# 3_Controller_A20_Ethernet.net
KiCad netlist of a schematic drawn in Altium Designer
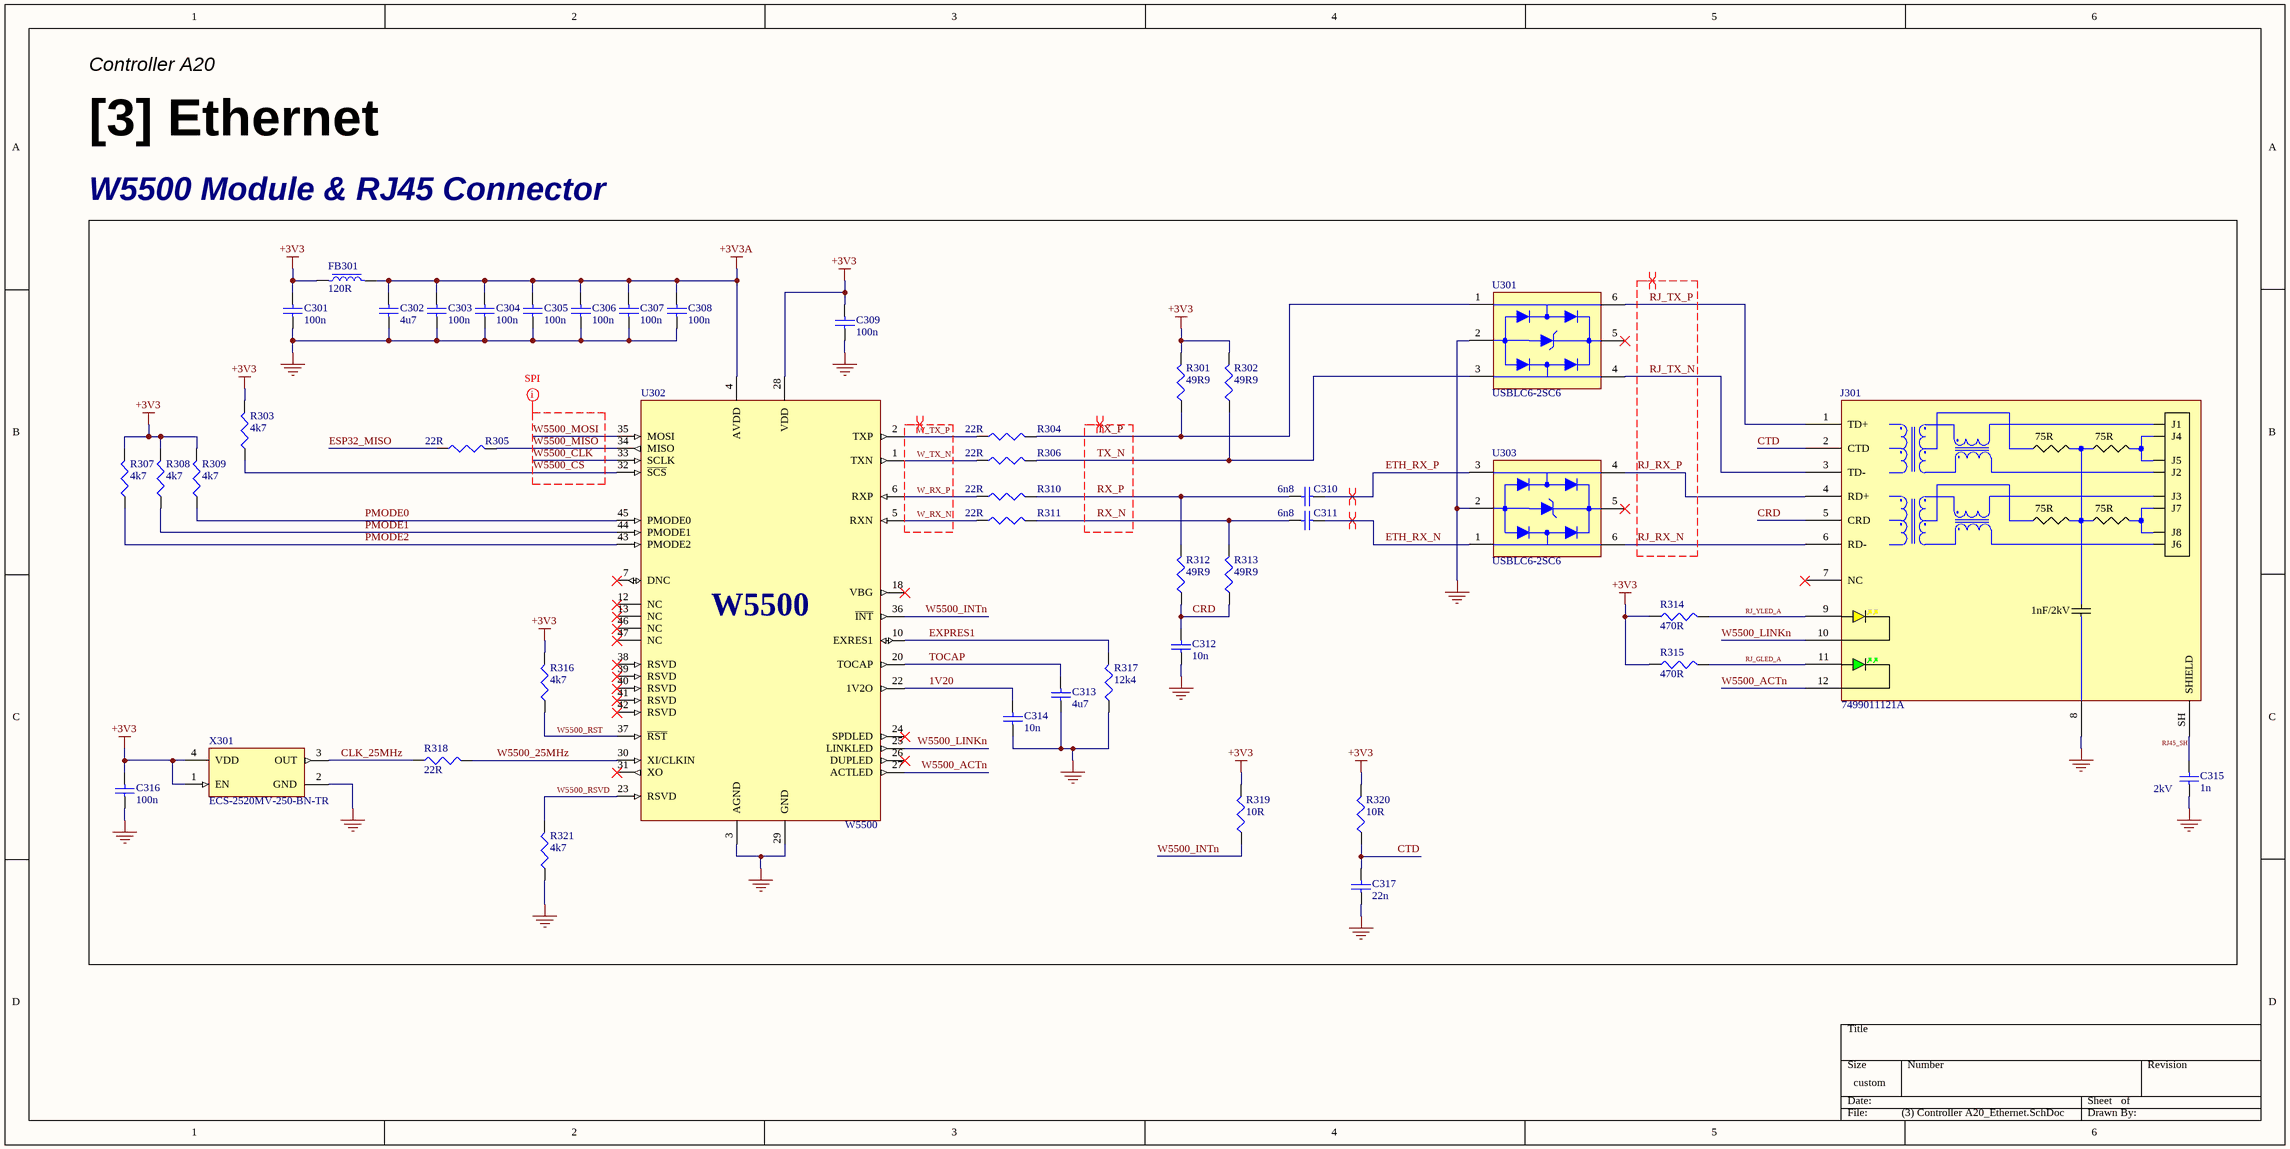
[diagram p0: (3) Controller A20_Ethernet.SchDoc]

(export (version "E")
  (design (tool "Eeschema 10.0.6"))
  (components
    (comp (ref "C301")
      (value "100n")
      (footprint "C0603")
      (description "0.1 µF ±10% 50V Ceramic Capacitor X7R 0603 (1608 Metric)")
      (fields (field (name "MANUFACTURER") "KEMET") (field (name "MFR. PART #") "C0603C104K5RACTU"))
      (libsource (lib "Symbols") (part "CAP 100nF 50V"))
    )
    (comp (ref "C302")
      (value "4u7")
      (footprint "C0805")
      (description "4.7 µF ±20% 50V Ceramic Capacitor X7R 0805 (2012 Metric)")
      (fields
        (field (name "MANUFACTURER") "Murata Electronics")
        (field (name "MFR. PART #") "GRM21BZ71H475ME15K")
      )
      (libsource (lib "Symbols") (part "CAP 4.7uF 50V"))
    )
    (comp (ref "C303")
      (value "100n")
      (footprint "C0603")
      (description "0.1 µF ±10% 50V Ceramic Capacitor X7R 0603 (1608 Metric)")
      (fields (field (name "MANUFACTURER") "KEMET") (field (name "MFR. PART #") "C0603C104K5RACTU"))
      (libsource (lib "Symbols") (part "CAP 100nF 50V"))
    )
    (comp (ref "C304")
      (value "100n")
      (footprint "C0603")
      (description "0.1 µF ±10% 50V Ceramic Capacitor X7R 0603 (1608 Metric)")
      (fields (field (name "MANUFACTURER") "KEMET") (field (name "MFR. PART #") "C0603C104K5RACTU"))
      (libsource (lib "Symbols") (part "CAP 100nF 50V"))
    )
    (comp (ref "C305")
      (value "100n")
      (footprint "C0603")
      (description "0.1 µF ±10% 50V Ceramic Capacitor X7R 0603 (1608 Metric)")
      (fields (field (name "MANUFACTURER") "KEMET") (field (name "MFR. PART #") "C0603C104K5RACTU"))
      (libsource (lib "Symbols") (part "CAP 100nF 50V"))
    )
    (comp (ref "C306")
      (value "100n")
      (footprint "C0603")
      (description "0.1 µF ±10% 50V Ceramic Capacitor X7R 0603 (1608 Metric)")
      (fields (field (name "MANUFACTURER") "KEMET") (field (name "MFR. PART #") "C0603C104K5RACTU"))
      (libsource (lib "Symbols") (part "CAP 100nF 50V"))
    )
    (comp (ref "C307")
      (value "100n")
      (footprint "C0603")
      (description "0.1 µF ±10% 50V Ceramic Capacitor X7R 0603 (1608 Metric)")
      (fields (field (name "MANUFACTURER") "KEMET") (field (name "MFR. PART #") "C0603C104K5RACTU"))
      (libsource (lib "Symbols") (part "CAP 100nF 50V"))
    )
    (comp (ref "C308")
      (value "100n")
      (footprint "C0603")
      (description "0.1 µF ±10% 50V Ceramic Capacitor X7R 0603 (1608 Metric)")
      (fields (field (name "MANUFACTURER") "KEMET") (field (name "MFR. PART #") "C0603C104K5RACTU"))
      (libsource (lib "Symbols") (part "CAP 100nF 50V"))
    )
    (comp (ref "C309")
      (value "100n")
      (footprint "C0603")
      (description "0.1 µF ±10% 50V Ceramic Capacitor X7R 0603 (1608 Metric)")
      (fields (field (name "MANUFACTURER") "KEMET") (field (name "MFR. PART #") "C0603C104K5RACTU"))
      (libsource (lib "Symbols") (part "CAP 100nF 50V"))
    )
    (comp (ref "C310")
      (value "6n8")
      (footprint "C0402")
      (description "6800 pF ±10% 100V Ceramic Capacitor X7R 0402 (1005 Metric)")
      (fields
        (field (name "MANUFACTURER") "Samsung Electro-Mechanics")
        (field (name "MFR. PART #") "CL05B682KC5VPNC")
      )
      (libsource (lib "Symbols") (part "CAP 6.8nF 100V"))
    )
    (comp (ref "C311")
      (value "6n8")
      (footprint "C0402")
      (description "6800 pF ±10% 100V Ceramic Capacitor X7R 0402 (1005 Metric)")
      (fields
        (field (name "MANUFACTURER") "Samsung Electro-Mechanics")
        (field (name "MFR. PART #") "CL05B682KC5VPNC")
      )
      (libsource (lib "Symbols") (part "CAP 6.8nF 100V"))
    )
    (comp (ref "C312")
      (value "10n")
      (footprint "C0402")
      (description "10000 pF ±10% 50V Ceramic Capacitor X7R 0402 (1005 Metric)")
      (fields (field (name "MANUFACTURER") "KEMET") (field (name "MFR. PART #") "C0402C103K5REC7411"))
      (libsource (lib "Symbols") (part "CAP 10nF 50V"))
    )
    (comp (ref "C313")
      (value "4u7")
      (footprint "C0805")
      (description "4.7 µF ±20% 50V Ceramic Capacitor X7R 0805 (2012 Metric)")
      (fields
        (field (name "MANUFACTURER") "Murata Electronics")
        (field (name "MFR. PART #") "GRM21BZ71H475ME15K")
      )
      (libsource (lib "Symbols") (part "CAP 4.7uF 50V"))
    )
    (comp (ref "C314")
      (value "10n")
      (footprint "C0402")
      (description "10000 pF ±10% 50V Ceramic Capacitor X7R 0402 (1005 Metric)")
      (fields (field (name "MANUFACTURER") "KEMET") (field (name "MFR. PART #") "C0402C103K5REC7411"))
      (libsource (lib "Symbols") (part "CAP 10nF 50V"))
    )
    (comp (ref "C315")
      (value "1n")
      (footprint "C1206")
      (description "2kV 1nF X7R ±10% 1206 Multilayer Ceramic Capacitors MLCC - SMD/SMT ROHS")
      (fields
        (field (name "MANUFACTURER") "Johanson Dielectrics")
        (field (name "MFR. PART #") "202R18W102KV4E")
      )
      (libsource (lib "Symbols") (part "CAP 1nF 2kV"))
    )
    (comp (ref "C316")
      (value "100n")
      (footprint "C0603")
      (description "0.1 µF ±10% 50V Ceramic Capacitor X7R 0603 (1608 Metric)")
      (fields (field (name "MANUFACTURER") "KEMET") (field (name "MFR. PART #") "C0603C104K5RACTU"))
      (libsource (lib "Symbols") (part "CAP 100nF 50V"))
    )
    (comp (ref "C317")
      (value "22n")
      (footprint "C0402")
      (description "0.022 µF ±10% 50V Ceramic Capacitor X7R 0402 (1005 Metric)")
      (fields (field (name "MANUFACTURER") "YAGEO") (field (name "MFR. PART #") "CC0402KRX7R9BB223"))
      (libsource (lib "Symbols") (part "CAP 22nF 50V"))
    )
    (comp (ref "FB301")
      (value "120R")
      (footprint "FB0402")
      (description "120 Ohms @ 100 MHz 1 Power Line Ferrite Bead 0402 (1005 Metric) 2A 55mOhm")
      (fields
        (field (name "MANUFACTURER") "Murata Electronics")
        (field (name "MFR. PART #") "BLM15PX121SN1D")
      )
      (libsource (lib "Symbols") (part "BLM15PX121SN1D Ferrite Bead 120Ω"))
    )
    (comp (ref "J301")
      (value "7499011121A")
      (footprint "RJ45 TH Connector")
      (description "1 Port RJ45 with Magnetics Through Hole 10/100 Base-T, AutoMDIX")
      (fields (field (name "MANUFACTURER") "Würth Elektronik"))
      (libsource (lib "Symbols") (part "7499011121A RJ45 Connector"))
    )
    (comp (ref "R301")
      (value "49R9")
      (footprint "R0402")
      (description "49.9 Ohms ±1% 0.063W, 1/16W Chip Resistor 0402 (1005 Metric) Moisture Resistant Thick Film")
      (fields (field (name "MANUFACTURER") "YAGEO") (field (name "MFR. PART #") "RC0402FR-0749R9L"))
      (libsource (lib "Symbols") (part "RES 49.9R"))
    )
    (comp (ref "R302")
      (value "49R9")
      (footprint "R0402")
      (description "49.9 Ohms ±1% 0.063W, 1/16W Chip Resistor 0402 (1005 Metric) Moisture Resistant Thick Film")
      (fields (field (name "MANUFACTURER") "YAGEO") (field (name "MFR. PART #") "RC0402FR-0749R9L"))
      (libsource (lib "Symbols") (part "RES 49.9R"))
    )
    (comp (ref "R303")
      (value "4k7")
      (footprint "R0603")
      (description "4.7 kOhms ±1% 0.1W, 1/10W Chip Resistor 0603 (1608 Metric) Moisture Resistant Thick Film")
      (fields (field (name "MANUFACTURER") "YAGEO") (field (name "MFR. PART #") "RC0603FR-074K7L"))
      (libsource (lib "Symbols") (part "RES 4.7k"))
    )
    (comp (ref "R304")
      (value "22R")
      (footprint "R0402")
      (description "22 Ohms ±1% 0.063W, 1/16W Chip Resistor 0402 (1005 Metric) Moisture Resistant Thick Film")
      (fields (field (name "MANUFACTURER") "YAGEO") (field (name "MFR. PART #") "RC0402FR-0722RL"))
      (libsource (lib "Symbols") (part "RES 22R"))
    )
    (comp (ref "R305")
      (value "22R")
      (footprint "R0402")
      (description "22 Ohms ±1% 0.063W, 1/16W Chip Resistor 0402 (1005 Metric) Moisture Resistant Thick Film")
      (fields (field (name "MANUFACTURER") "YAGEO") (field (name "MFR. PART #") "RC0402FR-0722RL"))
      (libsource (lib "Symbols") (part "RES 22R"))
    )
    (comp (ref "R306")
      (value "22R")
      (footprint "R0402")
      (description "22 Ohms ±1% 0.063W, 1/16W Chip Resistor 0402 (1005 Metric) Moisture Resistant Thick Film")
      (fields (field (name "MANUFACTURER") "YAGEO") (field (name "MFR. PART #") "RC0402FR-0722RL"))
      (libsource (lib "Symbols") (part "RES 22R"))
    )
    (comp (ref "R307")
      (value "4k7")
      (footprint "R0603")
      (description "4.7 kOhms ±1% 0.1W, 1/10W Chip Resistor 0603 (1608 Metric) Moisture Resistant Thick Film")
      (fields (field (name "MANUFACTURER") "YAGEO") (field (name "MFR. PART #") "RC0603FR-074K7L"))
      (libsource (lib "Symbols") (part "RES 4.7k"))
    )
    (comp (ref "R308")
      (value "4k7")
      (footprint "R0603")
      (description "4.7 kOhms ±1% 0.1W, 1/10W Chip Resistor 0603 (1608 Metric) Moisture Resistant Thick Film")
      (fields (field (name "MANUFACTURER") "YAGEO") (field (name "MFR. PART #") "RC0603FR-074K7L"))
      (libsource (lib "Symbols") (part "RES 4.7k"))
    )
    (comp (ref "R309")
      (value "4k7")
      (footprint "R0603")
      (description "4.7 kOhms ±1% 0.1W, 1/10W Chip Resistor 0603 (1608 Metric) Moisture Resistant Thick Film")
      (fields (field (name "MANUFACTURER") "YAGEO") (field (name "MFR. PART #") "RC0603FR-074K7L"))
      (libsource (lib "Symbols") (part "RES 4.7k"))
    )
    (comp (ref "R310")
      (value "22R")
      (footprint "R0402")
      (description "22 Ohms ±1% 0.063W, 1/16W Chip Resistor 0402 (1005 Metric) Moisture Resistant Thick Film")
      (fields (field (name "MANUFACTURER") "YAGEO") (field (name "MFR. PART #") "RC0402FR-0722RL"))
      (libsource (lib "Symbols") (part "RES 22R"))
    )
    (comp (ref "R311")
      (value "22R")
      (footprint "R0402")
      (description "22 Ohms ±1% 0.063W, 1/16W Chip Resistor 0402 (1005 Metric) Moisture Resistant Thick Film")
      (fields (field (name "MANUFACTURER") "YAGEO") (field (name "MFR. PART #") "RC0402FR-0722RL"))
      (libsource (lib "Symbols") (part "RES 22R"))
    )
    (comp (ref "R312")
      (value "49R9")
      (footprint "R0402")
      (description "49.9 Ohms ±1% 0.063W, 1/16W Chip Resistor 0402 (1005 Metric) Moisture Resistant Thick Film")
      (fields (field (name "MANUFACTURER") "YAGEO") (field (name "MFR. PART #") "RC0402FR-0749R9L"))
      (libsource (lib "Symbols") (part "RES 49.9R"))
    )
    (comp (ref "R313")
      (value "49R9")
      (footprint "R0402")
      (description "49.9 Ohms ±1% 0.063W, 1/16W Chip Resistor 0402 (1005 Metric) Moisture Resistant Thick Film")
      (fields (field (name "MANUFACTURER") "YAGEO") (field (name "MFR. PART #") "RC0402FR-0749R9L"))
      (libsource (lib "Symbols") (part "RES 49.9R"))
    )
    (comp (ref "R314")
      (value "470R")
      (footprint "R0603")
      (description "470 Ohms ±1% 0.1W, 1/10W Chip Resistor 0603 (1608 Metric) Thin Film")
      (fields (field (name "MANUFACTURER") "YAGEO") (field (name "MFR. PART #") "RT0603FRE07470RL"))
      (libsource (lib "Symbols") (part "RES 470R"))
    )
    (comp (ref "R315")
      (value "470R")
      (footprint "R0603")
      (description "470 Ohms ±1% 0.1W, 1/10W Chip Resistor 0603 (1608 Metric) Thin Film")
      (fields (field (name "MANUFACTURER") "YAGEO") (field (name "MFR. PART #") "RT0603FRE07470RL"))
      (libsource (lib "Symbols") (part "RES 470R"))
    )
    (comp (ref "R316")
      (value "4k7")
      (footprint "R0603")
      (description "4.7 kOhms ±1% 0.1W, 1/10W Chip Resistor 0603 (1608 Metric) Moisture Resistant Thick Film")
      (fields (field (name "MANUFACTURER") "YAGEO") (field (name "MFR. PART #") "RC0603FR-074K7L"))
      (libsource (lib "Symbols") (part "RES 4.7k"))
    )
    (comp (ref "R317")
      (value "12k4")
      (footprint "R0603")
      (description "12.4 kOhms ±1% 0.1W, 1/10W Chip Resistor 0603 (1608 Metric) Moisture Resistant Thick Film")
      (fields (field (name "MANUFACTURER") "YAGEO") (field (name "MFR. PART #") "RC0603FR-0712K4L"))
      (libsource (lib "Symbols") (part "RES 12.4k"))
    )
    (comp (ref "R318")
      (value "22R")
      (footprint "R0402")
      (description "22 Ohms ±1% 0.063W, 1/16W Chip Resistor 0402 (1005 Metric) Moisture Resistant Thick Film")
      (fields (field (name "MANUFACTURER") "YAGEO") (field (name "MFR. PART #") "RC0402FR-0722RL"))
      (libsource (lib "Symbols") (part "RES 22R"))
    )
    (comp (ref "R319")
      (value "10R")
      (footprint "R0402")
      (fields (field (name "MANUFACTURER") "YAGEO") (field (name "MFR. PART #") "AC0402FR-0710RL"))
      (libsource (lib "Symbols") (part "RES 10R"))
    )
    (comp (ref "R320")
      (value "10R")
      (footprint "R0402")
      (fields (field (name "MANUFACTURER") "YAGEO") (field (name "MFR. PART #") "AC0402FR-0710RL"))
      (libsource (lib "Symbols") (part "RES 10R"))
    )
    (comp (ref "R321")
      (value "4k7")
      (footprint "R0603")
      (description "4.7 kOhms ±1% 0.1W, 1/10W Chip Resistor 0603 (1608 Metric) Moisture Resistant Thick Film")
      (fields (field (name "MANUFACTURER") "YAGEO") (field (name "MFR. PART #") "RC0603FR-074K7L"))
      (libsource (lib "Symbols") (part "RES 4.7k"))
    )
    (comp (ref "U301")
      (value "USBLC6-2SC6")
      (footprint "SOT23-6L")
      (description "17V Clamp 5A (8/20µs) Ipp Tvs Diode Surface Mount SOT-23-6")
      (fields (field (name "MANUFACTURER") "STMicroelectronics"))
      (libsource (lib "") (part "USBLC6-2SC6 ESD Array 5.25VRWM_1"))
    )
    (comp (ref "U302")
      (value "W5500")
      (footprint "LQFP-48(7x7)")
      (description "Ethernet Controller 10/100 Base-T/TX PHY SPI Interface 48-LQFP (7x7)")
      (fields (field (name "MANUFACTURER") "WIZnet"))
      (libsource (lib "Symbols") (part "W5500 SPI to Ethernet"))
    )
    (comp (ref "U303")
      (value "USBLC6-2SC6")
      (footprint "SOT23-6L")
      (description "17V Clamp 5A (8/20µs) Ipp Tvs Diode Surface Mount SOT-23-6")
      (fields (field (name "MANUFACTURER") "STMicroelectronics"))
      (libsource (lib "Symbols") (part "USBLC6-2SC6 ESD Array 5.25VRWM"))
    )
    (comp (ref "X301")
      (value "ECS-2520MV-250-BN-TR")
      (footprint "SMD2520-4P")
      (description "25 MHz XO (Standard) HCMOS Oscillator 1.6V ~ 3.6V Enable/Disable 4-SMD, No Lead")
      (fields (field (name "MANUFACTURER") "ECS Inc."))
      (libsource (lib "Symbols") (part "25MHz HCMOS Oscillator"))
    )
  )
  (nets
    (net (code "1") (name "+3V3") (class "Default")
      (node (ref "C301") (pin "2") (pinfunction "2_2") (pintype "passive"))
      (node (ref "C309") (pin "2") (pinfunction "2_2") (pintype "passive"))
      (node (ref "C316") (pin "2") (pinfunction "2_2") (pintype "passive"))
      (node (ref "FB301") (pin "1") (pinfunction "1_1") (pintype "passive"))
      (node (ref "R301") (pin "2") (pinfunction "2_2") (pintype "passive"))
      (node (ref "R302") (pin "2") (pinfunction "2_2") (pintype "passive"))
      (node (ref "R303") (pin "2") (pinfunction "2_2") (pintype "passive"))
      (node (ref "R307") (pin "2") (pinfunction "2_2") (pintype "passive"))
      (node (ref "R308") (pin "2") (pinfunction "2_2") (pintype "passive"))
      (node (ref "R309") (pin "2") (pinfunction "2_2") (pintype "passive"))
      (node (ref "R314") (pin "1") (pinfunction "1_1") (pintype "passive"))
      (node (ref "R315") (pin "1") (pinfunction "1_1") (pintype "passive"))
      (node (ref "R316") (pin "2") (pinfunction "2_2") (pintype "passive"))
      (node (ref "R319") (pin "2") (pinfunction "2_2") (pintype "passive"))
      (node (ref "R320") (pin "2") (pinfunction "2_2") (pintype "passive"))
      (node (ref "U302") (pin "28") (pinfunction "VDD_28") (pintype "power_in"))
      (node (ref "X301") (pin "1") (pinfunction "EN_1") (pintype "input"))
      (node (ref "X301") (pin "4") (pinfunction "VDD_4") (pintype "power_in"))
    )
    (net (code "2") (name "+3V3A") (class "Default")
      (node (ref "C302") (pin "2") (pinfunction "2_2") (pintype "passive"))
      (node (ref "C303") (pin "2") (pinfunction "2_2") (pintype "passive"))
      (node (ref "C304") (pin "2") (pinfunction "2_2") (pintype "passive"))
      (node (ref "C305") (pin "2") (pinfunction "2_2") (pintype "passive"))
      (node (ref "C306") (pin "2") (pinfunction "2_2") (pintype "passive"))
      (node (ref "C307") (pin "2") (pinfunction "2_2") (pintype "passive"))
      (node (ref "C308") (pin "2") (pinfunction "2_2") (pintype "passive"))
      (node (ref "FB301") (pin "2") (pinfunction "2_2") (pintype "passive"))
      (node (ref "U302") (pin "4") (pinfunction "AVDD_4") (pintype "power_in"))
    )
    (net (code "3") (name "/1V20") (class "Default")
      (node (ref "C314") (pin "2") (pinfunction "2_2") (pintype "passive"))
      (node (ref "U302") (pin "22") (pinfunction "1V2O_22") (pintype "output"))
    )
    (net (code "4") (name "/CLK_25MHz") (class "Default")
      (node (ref "R318") (pin "1") (pinfunction "1_1") (pintype "passive"))
      (node (ref "X301") (pin "3") (pinfunction "OUT_3") (pintype "output"))
    )
    (net (code "5") (name "/CRD") (class "Default")
      (node (ref "C312") (pin "2") (pinfunction "2_2") (pintype "passive"))
      (node (ref "J301") (pin "5") (pinfunction "CRD_5") (pintype "passive"))
      (node (ref "R312") (pin "1") (pinfunction "1_1") (pintype "passive"))
      (node (ref "R313") (pin "1") (pinfunction "1_1") (pintype "passive"))
    )
    (net (code "6") (name "/CTD") (class "Default")
      (node (ref "C317") (pin "2") (pinfunction "2_2") (pintype "passive"))
      (node (ref "J301") (pin "2") (pinfunction "CTD_2") (pintype "passive"))
      (node (ref "R320") (pin "1") (pinfunction "1_1") (pintype "passive"))
    )
    (net (code "7") (name "/ESP32_MISO") (class "Default")
      (node (ref "R305") (pin "1") (pinfunction "1_1") (pintype "passive"))
    )
    (net (code "8") (name "/ETH_RX_N") (class "Default")
      (node (ref "C311") (pin "2") (pinfunction "2_2") (pintype "passive"))
      (node (ref "U303") (pin "1") (pinfunction "1_1") (pintype "passive"))
    )
    (net (code "9") (name "/ETH_RX_P") (class "Default")
      (node (ref "C310") (pin "2") (pinfunction "2_2") (pintype "passive"))
      (node (ref "U303") (pin "3") (pinfunction "3_3") (pintype "passive"))
    )
    (net (code "10") (name "/EXPRES1") (class "Default")
      (node (ref "R317") (pin "2") (pinfunction "2_2") (pintype "passive"))
      (node (ref "U302") (pin "10") (pinfunction "EXRES1_10") (pintype "bidirectional"))
    )
    (net (code "11") (name "/PMODE0") (class "Default")
      (node (ref "R309") (pin "1") (pinfunction "1_1") (pintype "passive"))
      (node (ref "U302") (pin "45") (pinfunction "PMODE0_45") (pintype "input"))
    )
    (net (code "12") (name "/PMODE1") (class "Default")
      (node (ref "R308") (pin "1") (pinfunction "1_1") (pintype "passive"))
      (node (ref "U302") (pin "44") (pinfunction "PMODE1_44") (pintype "input"))
    )
    (net (code "13") (name "/PMODE2") (class "Default")
      (node (ref "R307") (pin "1") (pinfunction "1_1") (pintype "passive"))
      (node (ref "U302") (pin "43") (pinfunction "PMODE2_43") (pintype "input"))
    )
    (net (code "14") (name "/RJ45_SH") (class "Default")
      (node (ref "C315") (pin "2") (pinfunction "2_2") (pintype "passive"))
      (node (ref "J301") (pin "SH") (pinfunction "SHIELD_SH") (pintype "passive"))
    )
    (net (code "15") (name "/RJ_GLED_A") (class "Default")
      (node (ref "J301") (pin "11") (pinfunction "G_LED_A_11") (pintype "passive"))
      (node (ref "R315") (pin "2") (pinfunction "2_2") (pintype "passive"))
    )
    (net (code "16") (name "/RJ_RX_N") (class "Default")
      (node (ref "J301") (pin "6") (pinfunction "RD-_6") (pintype "passive"))
      (node (ref "U303") (pin "6") (pinfunction "6_6") (pintype "passive"))
    )
    (net (code "17") (name "/RJ_RX_P") (class "Default")
      (node (ref "J301") (pin "4") (pinfunction "RD+_4") (pintype "passive"))
      (node (ref "U303") (pin "4") (pinfunction "4_4") (pintype "passive"))
    )
    (net (code "18") (name "/RJ_TX_N") (class "Default")
      (node (ref "J301") (pin "3") (pinfunction "TD-_3") (pintype "passive"))
      (node (ref "U301") (pin "4") (pinfunction "4_4") (pintype "passive"))
    )
    (net (code "19") (name "/RJ_TX_P") (class "Default")
      (node (ref "J301") (pin "1") (pinfunction "TD+_1") (pintype "passive"))
      (node (ref "U301") (pin "6") (pinfunction "6_6") (pintype "passive"))
    )
    (net (code "20") (name "/RJ_YLED_A") (class "Default")
      (node (ref "J301") (pin "9") (pinfunction "Y_LED_A_9") (pintype "passive"))
      (node (ref "R314") (pin "2") (pinfunction "2_2") (pintype "passive"))
    )
    (net (code "21") (name "/RX_N") (class "Default")
      (node (ref "C311") (pin "1") (pinfunction "1_1") (pintype "passive"))
      (node (ref "R311") (pin "2") (pinfunction "2_2") (pintype "passive"))
      (node (ref "R313") (pin "2") (pinfunction "2_2") (pintype "passive"))
    )
    (net (code "22") (name "/RX_P") (class "Default")
      (node (ref "C310") (pin "1") (pinfunction "1_1") (pintype "passive"))
      (node (ref "R310") (pin "2") (pinfunction "2_2") (pintype "passive"))
      (node (ref "R312") (pin "2") (pinfunction "2_2") (pintype "passive"))
    )
    (net (code "23") (name "/TOCAP") (class "Default")
      (node (ref "C313") (pin "2") (pinfunction "2_2") (pintype "passive"))
      (node (ref "U302") (pin "20") (pinfunction "TOCAP_20") (pintype "output"))
    )
    (net (code "24") (name "/TX_N") (class "Default")
      (node (ref "R302") (pin "1") (pinfunction "1_1") (pintype "passive"))
      (node (ref "R306") (pin "2") (pinfunction "2_2") (pintype "passive"))
      (node (ref "U301") (pin "3") (pinfunction "3_3") (pintype "passive"))
    )
    (net (code "25") (name "/TX_P") (class "Default")
      (node (ref "R301") (pin "1") (pinfunction "1_1") (pintype "passive"))
      (node (ref "R304") (pin "2") (pinfunction "2_2") (pintype "passive"))
      (node (ref "U301") (pin "1") (pinfunction "1_1") (pintype "passive"))
    )
    (net (code "26") (name "/W5500_25MHz") (class "Default")
      (node (ref "R318") (pin "2") (pinfunction "2_2") (pintype "passive"))
      (node (ref "U302") (pin "30") (pinfunction "XI/CLKIN_30") (pintype "input"))
    )
    (net (code "27") (name "/W5500_ACTn") (class "Default")
      (node (ref "J301") (pin "12") (pinfunction "G_LED_K_12") (pintype "passive"))
      (node (ref "U302") (pin "27") (pinfunction "ACTLED_27") (pintype "output"))
    )
    (net (code "28") (name "/W5500_CLK") (class "Default")
      (node (ref "U302") (pin "33") (pinfunction "SCLK_33") (pintype "input"))
    )
    (net (code "29") (name "/W5500_CS") (class "Default")
      (node (ref "R303") (pin "1") (pinfunction "1_1") (pintype "passive"))
      (node (ref "U302") (pin "32") (pinfunction "~{SCS}_32") (pintype "input"))
    )
    (net (code "30") (name "/W5500_INTn") (class "Default")
      (node (ref "R319") (pin "1") (pinfunction "1_1") (pintype "passive"))
      (node (ref "U302") (pin "36") (pinfunction "~{INT}_36") (pintype "output"))
    )
    (net (code "31") (name "/W5500_LINKn") (class "Default")
      (node (ref "J301") (pin "10") (pinfunction "Y_LED_K_10") (pintype "passive"))
      (node (ref "U302") (pin "25") (pinfunction "LINKLED_25") (pintype "output"))
    )
    (net (code "32") (name "/W5500_MISO") (class "Default")
      (node (ref "R305") (pin "2") (pinfunction "2_2") (pintype "passive"))
      (node (ref "U302") (pin "34") (pinfunction "MISO_34") (pintype "output"))
    )
    (net (code "33") (name "/W5500_MOSI") (class "Default")
      (node (ref "U302") (pin "35") (pinfunction "MOSI_35") (pintype "input"))
    )
    (net (code "34") (name "/W5500_RST") (class "Default")
      (node (ref "R316") (pin "1") (pinfunction "1_1") (pintype "passive"))
      (node (ref "U302") (pin "37") (pinfunction "~{RST}_37") (pintype "input"))
    )
    (net (code "35") (name "/W5500_RSVD") (class "Default")
      (node (ref "R321") (pin "2") (pinfunction "2_2") (pintype "passive"))
      (node (ref "U302") (pin "23") (pinfunction "RSVD_23") (pintype "input"))
    )
    (net (code "36") (name "/W_RX_N") (class "Default")
      (node (ref "R311") (pin "1") (pinfunction "1_1") (pintype "passive"))
      (node (ref "U302") (pin "5") (pinfunction "RXN_5") (pintype "input"))
    )
    (net (code "37") (name "/W_RX_P") (class "Default")
      (node (ref "R310") (pin "1") (pinfunction "1_1") (pintype "passive"))
      (node (ref "U302") (pin "6") (pinfunction "RXP_6") (pintype "input"))
    )
    (net (code "38") (name "/W_TX_N") (class "Default")
      (node (ref "R306") (pin "1") (pinfunction "1_1") (pintype "passive"))
      (node (ref "U302") (pin "1") (pinfunction "TXN_1") (pintype "output"))
    )
    (net (code "39") (name "/W_TX_P") (class "Default")
      (node (ref "R304") (pin "1") (pinfunction "1_1") (pintype "passive"))
      (node (ref "U302") (pin "2") (pinfunction "TXP_2") (pintype "output"))
    )
    (net (code "40") (name "GND") (class "Default")
      (node (ref "C301") (pin "1") (pinfunction "1_1") (pintype "passive"))
      (node (ref "C302") (pin "1") (pinfunction "1_1") (pintype "passive"))
      (node (ref "C303") (pin "1") (pinfunction "1_1") (pintype "passive"))
      (node (ref "C304") (pin "1") (pinfunction "1_1") (pintype "passive"))
      (node (ref "C305") (pin "1") (pinfunction "1_1") (pintype "passive"))
      (node (ref "C306") (pin "1") (pinfunction "1_1") (pintype "passive"))
      (node (ref "C307") (pin "1") (pinfunction "1_1") (pintype "passive"))
      (node (ref "C308") (pin "1") (pinfunction "1_1") (pintype "passive"))
      (node (ref "C309") (pin "1") (pinfunction "1_1") (pintype "passive"))
      (node (ref "C312") (pin "1") (pinfunction "1_1") (pintype "passive"))
      (node (ref "C313") (pin "1") (pinfunction "1_1") (pintype "passive"))
      (node (ref "C314") (pin "1") (pinfunction "1_1") (pintype "passive"))
      (node (ref "C315") (pin "1") (pinfunction "1_1") (pintype "passive"))
      (node (ref "C316") (pin "1") (pinfunction "1_1") (pintype "passive"))
      (node (ref "C317") (pin "1") (pinfunction "1_1") (pintype "passive"))
      (node (ref "J301") (pin "8") (pinfunction "8_8") (pintype "passive"))
      (node (ref "R317") (pin "1") (pinfunction "1_1") (pintype "passive"))
      (node (ref "R321") (pin "1") (pinfunction "1_1") (pintype "passive"))
      (node (ref "U301") (pin "2") (pinfunction "2_2") (pintype "passive"))
      (node (ref "U302") (pin "29") (pinfunction "GND_29") (pintype "power_in"))
      (node (ref "U302") (pin "3") (pinfunction "AGND_3") (pintype "power_in"))
      (node (ref "U303") (pin "2") (pinfunction "2_2") (pintype "passive"))
      (node (ref "X301") (pin "2") (pinfunction "GND_2") (pintype "power_in"))
    )
    (net (code "41") (name "unconnected-(J301-NC-Pad7)") (class "Default")
      (node (ref "J301") (pin "7") (pinfunction "NC_7") (pintype "passive+no_connect"))
    )
    (net (code "42") (name "unconnected-(U301-Pad5)") (class "Default")
      (node (ref "U301") (pin "5") (pinfunction "5_5") (pintype "passive+no_connect"))
    )
    (net (code "43") (name "unconnected-(U302-DNC-Pad7)") (class "Default")
      (node (ref "U302") (pin "7") (pinfunction "DNC_7") (pintype "bidirectional+no_connect"))
    )
    (net (code "44") (name "unconnected-(U302-DUPLED-Pad26)") (class "Default")
      (node (ref "U302") (pin "26") (pinfunction "DUPLED_26") (pintype "output+no_connect"))
    )
    (net (code "45") (name "unconnected-(U302-NC-Pad12)") (class "Default")
      (node (ref "U302") (pin "12") (pinfunction "NC_12") (pintype "tri_state+no_connect"))
    )
    (net (code "46") (name "unconnected-(U302-NC-Pad13)") (class "Default")
      (node (ref "U302") (pin "13") (pinfunction "NC_13") (pintype "tri_state+no_connect"))
    )
    (net (code "47") (name "unconnected-(U302-NC-Pad46)") (class "Default")
      (node (ref "U302") (pin "46") (pinfunction "NC_46") (pintype "tri_state+no_connect"))
    )
    (net (code "48") (name "unconnected-(U302-NC-Pad47)") (class "Default")
      (node (ref "U302") (pin "47") (pinfunction "NC_47") (pintype "tri_state+no_connect"))
    )
    (net (code "49") (name "unconnected-(U302-RSVD-Pad38)") (class "Default")
      (node (ref "U302") (pin "38") (pinfunction "RSVD_38") (pintype "input+no_connect"))
    )
    (net (code "50") (name "unconnected-(U302-RSVD-Pad39)") (class "Default")
      (node (ref "U302") (pin "39") (pinfunction "RSVD_39") (pintype "input+no_connect"))
    )
    (net (code "51") (name "unconnected-(U302-RSVD-Pad40)") (class "Default")
      (node (ref "U302") (pin "40") (pinfunction "RSVD_40") (pintype "input+no_connect"))
    )
    (net (code "52") (name "unconnected-(U302-RSVD-Pad41)") (class "Default")
      (node (ref "U302") (pin "41") (pinfunction "RSVD_41") (pintype "input+no_connect"))
    )
    (net (code "53") (name "unconnected-(U302-RSVD-Pad42)") (class "Default")
      (node (ref "U302") (pin "42") (pinfunction "RSVD_42") (pintype "input+no_connect"))
    )
    (net (code "54") (name "unconnected-(U302-SPDLED-Pad24)") (class "Default")
      (node (ref "U302") (pin "24") (pinfunction "SPDLED_24") (pintype "output+no_connect"))
    )
    (net (code "55") (name "unconnected-(U302-VBG-Pad18)") (class "Default")
      (node (ref "U302") (pin "18") (pinfunction "VBG_18") (pintype "output+no_connect"))
    )
    (net (code "56") (name "unconnected-(U302-XO-Pad31)") (class "Default")
      (node (ref "U302") (pin "31") (pinfunction "XO_31") (pintype "output+no_connect"))
    )
    (net (code "57") (name "unconnected-(U303-Pad5)") (class "Default")
      (node (ref "U303") (pin "5") (pinfunction "5_5") (pintype "passive+no_connect"))
    )
  )
)
